# ESP8266_144.net
KiCad netlist of a schematic drawn in Altium Designer
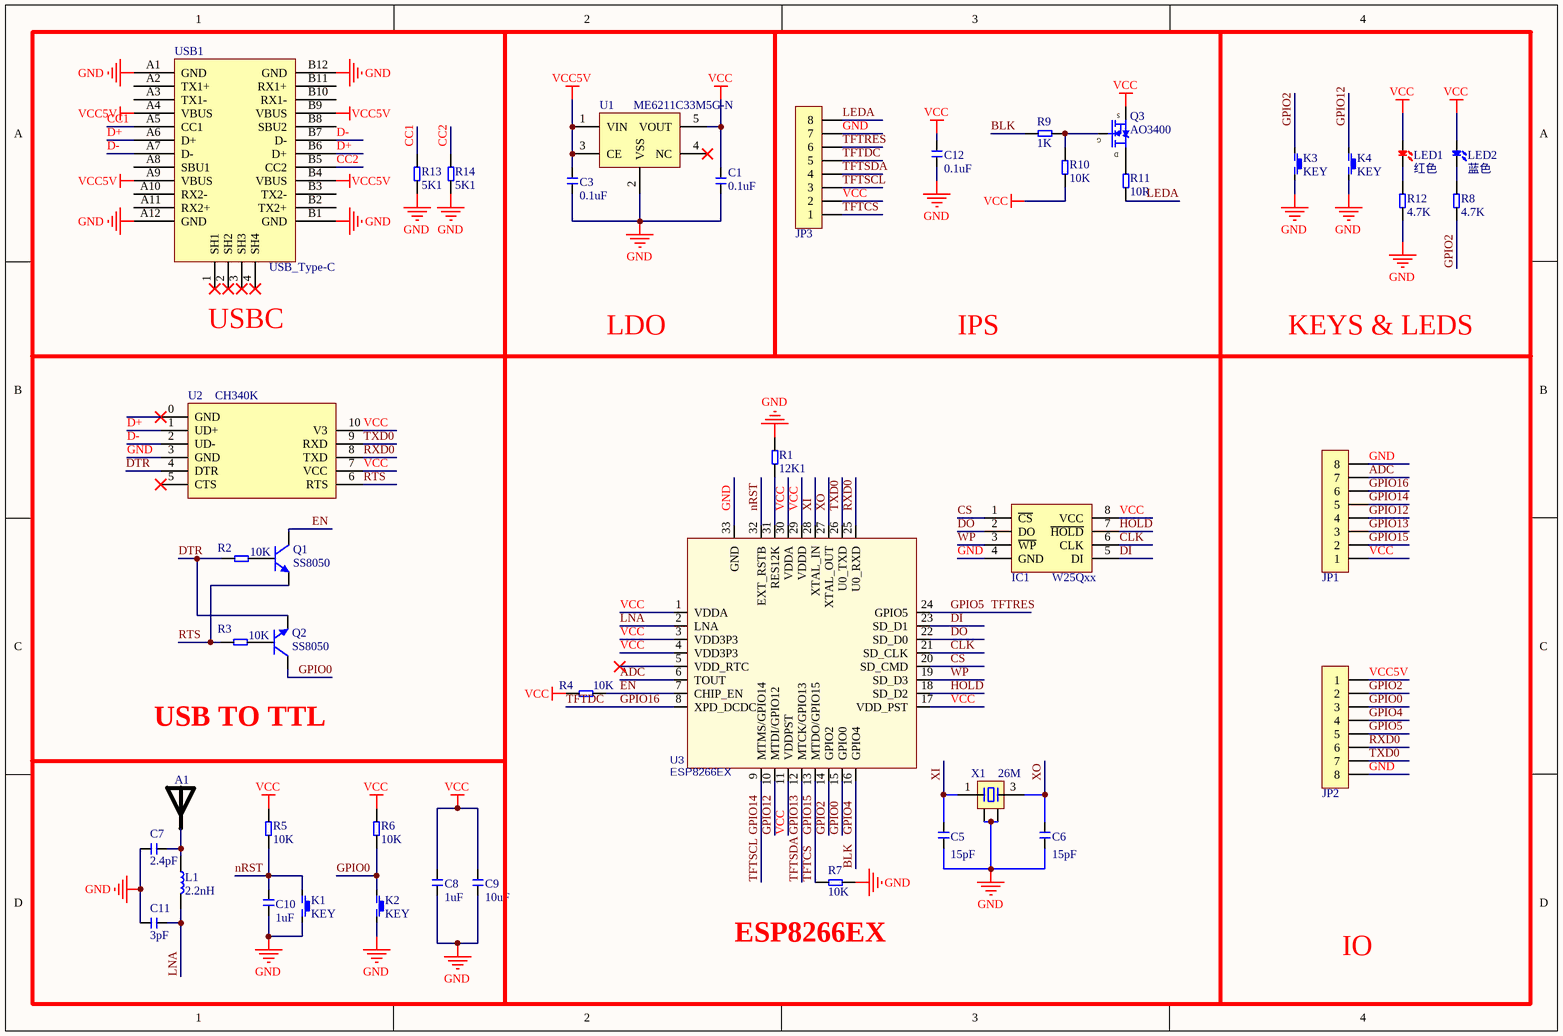
[diagram p0: ESP8266_144.SchDoc]

(export (version "E")
  (design (tool "Eeschema 10.0.6"))
  (components
    (comp (ref "A1")
      (value "RAINSUN")
      (footprint "PCBComponent_1")
      (libsource (lib "MyPcbLib") (part "ANT-Rainsun-AP5120"))
    )
    (comp (ref "C1")
      (value "0.1uF")
      (footprint "C 0603_M")
      (description "无极性贴片电容")
      (fields (field (name "版权归属") "源创客"))
      (libsource (lib "3   电容电阻电感跳线") (part "C"))
    )
    (comp (ref "C3")
      (value "0.1uF")
      (footprint "C 0603_M")
      (description "无极性贴片电容")
      (fields (field (name "版权归属") "源创客"))
      (libsource (lib "3   电容电阻电感跳线") (part "C"))
    )
    (comp (ref "C5")
      (value "15pF")
      (footprint "C 0603_M")
      (description "无极性贴片电容")
      (fields (field (name "版权归属") "源创客"))
      (libsource (lib "3   电容电阻电感跳线") (part "C"))
    )
    (comp (ref "C6")
      (value "15pF")
      (footprint "C 0603_M")
      (description "无极性贴片电容")
      (fields (field (name "版权归属") "源创客"))
      (libsource (lib "3   电容电阻电感跳线") (part "C"))
    )
    (comp (ref "C7")
      (value "2.4pF")
      (footprint "C 0603_M")
      (description "无极性贴片电容")
      (fields (field (name "版权归属") "源创客"))
      (libsource (lib "3   电容电阻电感跳线") (part "C"))
    )
    (comp (ref "C8")
      (value "1uF")
      (footprint "C 0603_M")
      (description "无极性贴片电容")
      (fields (field (name "版权归属") "源创客"))
      (libsource (lib "3   电容电阻电感跳线") (part "C"))
    )
    (comp (ref "C9")
      (value "10uF")
      (footprint "C 0603_M")
      (description "无极性贴片电容")
      (fields (field (name "版权归属") "源创客"))
      (libsource (lib "3   电容电阻电感跳线") (part "C"))
    )
    (comp (ref "C10")
      (value "1uF")
      (footprint "C 0603_M")
      (description "无极性贴片电容")
      (fields (field (name "版权归属") "源创客"))
      (libsource (lib "3   电容电阻电感跳线") (part "C"))
    )
    (comp (ref "C11")
      (value "3pF")
      (footprint "C 0603_M")
      (description "无极性贴片电容")
      (fields (field (name "版权归属") "源创客"))
      (libsource (lib "3   电容电阻电感跳线") (part "C"))
    )
    (comp (ref "C12")
      (value "0.1uF")
      (footprint "C 0603_M")
      (description "无极性贴片电容")
      (fields (field (name "版权归属") "源创客"))
      (libsource (lib "3   电容电阻电感跳线") (part "C"))
    )
    (comp (ref "IC1")
      (value "W25Qxx")
      (footprint "SOP8W_L")
      (description "外置Flash")
      (fields (field (name "版权归属") "源创客"))
      (libsource (lib "1   芯片") (part "W25Qxx"))
    )
    (comp (ref "JP1")
      (value "HDR-1X8")
      (footprint "HDR2.54-LI-8P")
      (description "8P接插件")
      (fields (field (name "版权归属") "源创客"))
      (libsource (lib "4   插接件") (part "W2.54-Header 8"))
    )
    (comp (ref "JP2")
      (value "HDR-1X8")
      (footprint "HDR2.54-LI-8P")
      (description "8P接插件")
      (fields (field (name "版权归属") "源创客"))
      (libsource (lib "") (part "W2.54-Header 8_1"))
    )
    (comp (ref "JP3")
      (value "HDR-1X8")
      (footprint "1.14 IPS")
      (description "8P接插件")
      (fields (field (name "版权归属") "源创客"))
      (libsource (lib "4   插接件") (part "W2.54-Header 8"))
    )
    (comp (ref "K1") (value "KEY") (footprint "KEY 4.2*3.2*2.5") (libsource (lib "ESP8266核心板") (part "KEY")))
    (comp (ref "K2") (value "KEY") (footprint "KEY 4.2*3.2*2.5") (libsource (lib "ESP8266核心板") (part "KEY")))
    (comp (ref "K3") (value "KEY") (footprint "KEY 4.2*3.2*2.5") (libsource (lib "ESP8266核心板") (part "KEY")))
    (comp (ref "K4") (value "KEY") (footprint "KEY 4.2*3.2*2.5") (libsource (lib "ESP8266核心板") (part "KEY")))
    (comp (ref "L1")
      (value "2.2nH")
      (footprint "L 0603_M")
      (description "小功率贴片电感")
      (fields (field (name "版权归属") "源创客"))
      (libsource (lib "3   电容电阻电感跳线") (part "L"))
    )
    (comp (ref "LED1")
      (value "红色")
      (footprint "LED 0603R_M")
      (description "贴片LED")
      (fields (field (name "版权归属") "源创客"))
      (libsource (lib "9   显示器件") (part "LED-SMD_R"))
    )
    (comp (ref "LED2")
      (value "蓝色")
      (footprint "LED 0603B_M")
      (description "贴片LED")
      (fields (field (name "版权归属") "源创客"))
      (libsource (lib "9   显示器件") (part "LED-SMD_B"))
    )
    (comp (ref "Q1")
      (value "SS8050")
      (footprint "SOT23-3M")
      (description "高频放大-NPN型")
      (fields (field (name "版权归属") "源创客"))
      (libsource (lib "6   半导体分立元件") (part "8050-SMD"))
    )
    (comp (ref "Q2")
      (value "SS8050")
      (footprint "SOT23-3M")
      (description "高频放大-NPN型")
      (fields (field (name "版权归属") "源创客"))
      (libsource (lib "6   半导体分立元件") (part "8050-SMD"))
    )
    (comp (ref "Q3")
      (value "AO3400")
      (footprint "SOT23-3M")
      (description "N沟道场效应管")
      (fields (field (name "版权归属") "源创客"))
      (libsource (lib "6   半导体分立元件") (part "AO3400"))
    )
    (comp (ref "R1") (value "12K1") (footprint "R 0603_M") (libsource (lib "measure_") (part "RES")))
    (comp (ref "R2") (value "10K") (footprint "R 0603_M") (libsource (lib "measure_") (part "RES")))
    (comp (ref "R3") (value "10K") (footprint "R 0603_M") (libsource (lib "measure_") (part "RES")))
    (comp (ref "R4") (value "10K") (footprint "R 0603_M") (libsource (lib "measure_") (part "RES")))
    (comp (ref "R5") (value "10K") (footprint "R 0603_M") (libsource (lib "measure_") (part "RES")))
    (comp (ref "R6") (value "10K") (footprint "R 0603_M") (libsource (lib "measure_") (part "RES")))
    (comp (ref "R7") (value "10K") (footprint "R 0603_M") (libsource (lib "measure_") (part "RES")))
    (comp (ref "R8") (value "4.7K") (footprint "R 0603_M") (libsource (lib "measure_") (part "RES")))
    (comp (ref "R9") (value "1K") (footprint "R 0603_M") (libsource (lib "measure_") (part "RES")))
    (comp (ref "R10") (value "10K") (footprint "R 0603_M") (libsource (lib "measure_") (part "RES")))
    (comp (ref "R11") (value "10R") (footprint "R 0603_M") (libsource (lib "measure_") (part "RES")))
    (comp (ref "R12") (value "4.7K") (footprint "R 0603_M") (libsource (lib "measure_") (part "RES")))
    (comp (ref "R13") (value "5K1") (footprint "R 0603_M") (libsource (lib "measure_") (part "RES")))
    (comp (ref "R14") (value "5K1") (footprint "R 0603_M") (libsource (lib "measure_") (part "RES")))
    (comp (ref "U1")
      (value "ME6211C33M5G-N")
      (footprint "SOT23-5N")
      (description "大电流高速LDO")
      (fields (field (name "版权归属") "源创客"))
      (libsource (lib "1   芯片") (part "XC6210B302"))
    )
    (comp (ref "U2") (value "CH340K") (footprint "CH340K") (libsource (lib "Schlib1") (part "CH340K")))
    (comp (ref "U3")
      (value "ESP8266EX")
      (footprint "QFN32 5x5_M")
      (fields (field (name "BOM_SUPPLIER PART") "C77967"))
      (libsource (lib "ESP8266核心板") (part "ESP8266EX"))
    )
    (comp (ref "USB1")
      (value "USB_Type-C")
      (footprint "TYPEC沉板")
      (libsource (lib "Vowstar_MCU") (part "USB_Type-C"))
    )
    (comp (ref "X1")
      (value "26M")
      (footprint "OSC 3225-4P")
      (description "4脚无源晶振")
      (fields (field (name "版权归属") "源创客"))
      (libsource (lib "10  保险丝 晶振") (part "XTAL-4P"))
    )
  )
  (nets
    (net (code "1") (name "/ADC") (class "Default")
      (node (ref "JP1") (pin "7") (pinfunction "7_7") (pintype "passive"))
      (node (ref "U3") (pin "6") (pinfunction "TOUT_6") (pintype "passive"))
    )
    (net (code "2") (name "/BLK") (class "Default")
      (node (ref "JP2") (pin "4") (pinfunction "4_4") (pintype "passive"))
      (node (ref "R9") (pin "1") (pintype "passive"))
      (node (ref "U3") (pin "16") (pinfunction "GPIO4_16") (pintype "passive"))
    )
    (net (code "3") (name "/CC1") (class "Default")
      (node (ref "R13") (pin "1") (pintype "passive"))
      (node (ref "USB1") (pin "A5") (pinfunction "CC1_A5") (pintype "passive"))
    )
    (net (code "4") (name "/CC2") (class "Default")
      (node (ref "R14") (pin "1") (pintype "passive"))
      (node (ref "USB1") (pin "B5") (pinfunction "CC2_B5") (pintype "passive"))
    )
    (net (code "5") (name "/CLK") (class "Default")
      (node (ref "IC1") (pin "6") (pinfunction "CLK_6") (pintype "passive"))
      (node (ref "U3") (pin "21") (pinfunction "SD_CLK_21") (pintype "passive"))
    )
    (net (code "6") (name "/CS") (class "Default")
      (node (ref "IC1") (pin "1") (pinfunction "~{CS}_1") (pintype "passive"))
      (node (ref "U3") (pin "20") (pinfunction "SD_CMD_20") (pintype "passive"))
    )
    (net (code "7") (name "/D+") (class "Default")
      (node (ref "U2") (pin "1") (pinfunction "UD+_1") (pintype "passive"))
      (node (ref "USB1") (pin "A6") (pinfunction "D+_A6") (pintype "passive"))
      (node (ref "USB1") (pin "B6") (pinfunction "D+_B6") (pintype "passive"))
    )
    (net (code "8") (name "/D-") (class "Default")
      (node (ref "U2") (pin "2") (pinfunction "UD-_2") (pintype "passive"))
      (node (ref "USB1") (pin "A7") (pinfunction "D-_A7") (pintype "passive"))
      (node (ref "USB1") (pin "B7") (pinfunction "D-_B7") (pintype "passive"))
    )
    (net (code "9") (name "/DI") (class "Default")
      (node (ref "IC1") (pin "5") (pinfunction "DI_5") (pintype "passive"))
      (node (ref "U3") (pin "23") (pinfunction "SD_D1_23") (pintype "passive"))
    )
    (net (code "10") (name "/DO") (class "Default")
      (node (ref "IC1") (pin "2") (pinfunction "DO_2") (pintype "passive"))
      (node (ref "U3") (pin "22") (pinfunction "SD_D0_22") (pintype "passive"))
    )
    (net (code "11") (name "/DTR") (class "Default")
      (node (ref "Q2") (pin "2") (pinfunction "E_2") (pintype "passive"))
      (node (ref "R2") (pin "2") (pintype "passive"))
      (node (ref "U2") (pin "4") (pinfunction "DTR_4") (pintype "passive"))
    )
    (net (code "12") (name "/EN") (class "Default")
      (node (ref "Q1") (pin "3") (pinfunction "C_3") (pintype "passive"))
      (node (ref "R4") (pin "2") (pintype "passive"))
      (node (ref "U3") (pin "7") (pinfunction "CHIP_EN_7") (pintype "passive"))
    )
    (net (code "13") (name "/GPIO0") (class "Default")
      (node (ref "JP2") (pin "3") (pinfunction "3_3") (pintype "passive"))
      (node (ref "K2") (pin "1") (pinfunction "1_1") (pintype "passive"))
      (node (ref "Q2") (pin "3") (pinfunction "C_3") (pintype "passive"))
      (node (ref "R6") (pin "2") (pintype "passive"))
      (node (ref "U3") (pin "15") (pinfunction "GPIO0_15") (pintype "passive"))
    )
    (net (code "14") (name "/GPIO2") (class "Default")
      (node (ref "JP2") (pin "2") (pinfunction "2_2") (pintype "passive"))
      (node (ref "K3") (pin "1") (pinfunction "1_1") (pintype "passive"))
      (node (ref "R8") (pin "2") (pintype "passive"))
      (node (ref "U3") (pin "14") (pinfunction "GPIO2_14") (pintype "passive"))
    )
    (net (code "15") (name "/GPIO5") (class "Default")
      (node (ref "JP2") (pin "5") (pinfunction "5_5") (pintype "passive"))
      (node (ref "JP3") (pin "6") (pinfunction "6_6") (pintype "passive"))
      (node (ref "U3") (pin "24") (pinfunction "GPIO5_24") (pintype "passive"))
    )
    (net (code "16") (name "/GPIO12") (class "Default")
      (node (ref "JP1") (pin "4") (pinfunction "4_4") (pintype "passive"))
      (node (ref "K4") (pin "1") (pinfunction "1_1") (pintype "passive"))
      (node (ref "U3") (pin "10") (pinfunction "MTDI/GPIO12_10") (pintype "passive"))
    )
    (net (code "17") (name "/GPIO13") (class "Default")
      (node (ref "JP1") (pin "3") (pinfunction "3_3") (pintype "passive"))
      (node (ref "JP3") (pin "4") (pinfunction "4_4") (pintype "passive"))
      (node (ref "U3") (pin "12") (pinfunction "MTCK/GPIO13_12") (pintype "passive"))
    )
    (net (code "18") (name "/GPIO14") (class "Default")
      (node (ref "JP1") (pin "5") (pinfunction "5_5") (pintype "passive"))
      (node (ref "JP3") (pin "3") (pinfunction "3_3") (pintype "passive"))
      (node (ref "U3") (pin "9") (pinfunction "MTMS/GPIO14_9") (pintype "passive"))
    )
    (net (code "19") (name "/GPIO15") (class "Default")
      (node (ref "JP1") (pin "2") (pinfunction "2_2") (pintype "passive"))
      (node (ref "JP3") (pin "1") (pinfunction "1_1") (pintype "passive"))
      (node (ref "R7") (pin "2") (pintype "passive"))
      (node (ref "U3") (pin "13") (pinfunction "MTDO/GPIO15_13") (pintype "passive"))
    )
    (net (code "20") (name "/GPIO16") (class "Default")
      (node (ref "JP1") (pin "6") (pinfunction "6_6") (pintype "passive"))
      (node (ref "JP3") (pin "5") (pinfunction "5_5") (pintype "passive"))
      (node (ref "U3") (pin "8") (pinfunction "XPD_DCDC_8") (pintype "passive"))
    )
    (net (code "21") (name "/HOLD") (class "Default")
      (node (ref "IC1") (pin "7") (pinfunction "~{HOLD}_7") (pintype "passive"))
      (node (ref "U3") (pin "18") (pinfunction "SD_D2_18") (pintype "passive"))
    )
    (net (code "22") (name "/LEDA") (class "Default")
      (node (ref "JP3") (pin "8") (pinfunction "8_8") (pintype "passive"))
      (node (ref "R11") (pin "1") (pintype "passive"))
    )
    (net (code "23") (name "/LNA") (class "Default")
      (node (ref "C11") (pin "1") (pinfunction "1_1") (pintype "passive"))
      (node (ref "L1") (pin "2") (pinfunction "2_2") (pintype "passive"))
      (node (ref "U3") (pin "2") (pinfunction "LNA_2") (pintype "passive"))
    )
    (net (code "24") (name "/RTS") (class "Default")
      (node (ref "Q1") (pin "2") (pinfunction "E_2") (pintype "passive"))
      (node (ref "R3") (pin "2") (pintype "passive"))
      (node (ref "U2") (pin "6") (pinfunction "RTS_6") (pintype "passive"))
    )
    (net (code "25") (name "/RXD0") (class "Default")
      (node (ref "JP2") (pin "6") (pinfunction "6_6") (pintype "passive"))
      (node (ref "U2") (pin "8") (pinfunction "TXD_8") (pintype "passive"))
      (node (ref "U3") (pin "25") (pinfunction "U0_RXD_25") (pintype "passive"))
    )
    (net (code "26") (name "/TXD0") (class "Default")
      (node (ref "JP2") (pin "7") (pinfunction "7_7") (pintype "passive"))
      (node (ref "U2") (pin "9") (pinfunction "RXD_9") (pintype "passive"))
      (node (ref "U3") (pin "26") (pinfunction "U0_TXD_26") (pintype "passive"))
    )
    (net (code "27") (name "/WP") (class "Default")
      (node (ref "IC1") (pin "3") (pinfunction "~{WP}_3") (pintype "passive"))
      (node (ref "U3") (pin "19") (pinfunction "SD_D3_19") (pintype "passive"))
    )
    (net (code "28") (name "/XI") (class "Default")
      (node (ref "C5") (pin "2") (pinfunction "2_2") (pintype "passive"))
      (node (ref "U3") (pin "28") (pinfunction "XTAL_IN_28") (pintype "passive"))
      (node (ref "X1") (pin "1") (pinfunction "1_1") (pintype "passive"))
    )
    (net (code "29") (name "/XO") (class "Default")
      (node (ref "C6") (pin "2") (pinfunction "2_2") (pintype "passive"))
      (node (ref "U3") (pin "27") (pinfunction "XTAL_OUT_27") (pintype "passive"))
      (node (ref "X1") (pin "3") (pinfunction "3_3") (pintype "passive"))
    )
    (net (code "30") (name "/nRST") (class "Default")
      (node (ref "C10") (pin "2") (pinfunction "2_2") (pintype "passive"))
      (node (ref "K1") (pin "1") (pinfunction "1_1") (pintype "passive"))
      (node (ref "R5") (pin "2") (pintype "passive"))
      (node (ref "U3") (pin "32") (pinfunction "EXT_RSTB_32") (pintype "passive"))
    )
    (net (code "31") (name "GND") (class "Default")
      (node (ref "C1") (pin "1") (pinfunction "1_1") (pintype "passive"))
      (node (ref "C10") (pin "1") (pinfunction "1_1") (pintype "passive"))
      (node (ref "C11") (pin "2") (pinfunction "2_2") (pintype "passive"))
      (node (ref "C12") (pin "1") (pinfunction "1_1") (pintype "passive"))
      (node (ref "C3") (pin "1") (pinfunction "1_1") (pintype "passive"))
      (node (ref "C5") (pin "1") (pinfunction "1_1") (pintype "passive"))
      (node (ref "C6") (pin "1") (pinfunction "1_1") (pintype "passive"))
      (node (ref "C7") (pin "2") (pinfunction "2_2") (pintype "passive"))
      (node (ref "C8") (pin "1") (pinfunction "1_1") (pintype "passive"))
      (node (ref "C9") (pin "1") (pinfunction "1_1") (pintype "passive"))
      (node (ref "IC1") (pin "4") (pinfunction "GND_4") (pintype "passive"))
      (node (ref "JP1") (pin "8") (pinfunction "8_8") (pintype "passive"))
      (node (ref "JP2") (pin "8") (pinfunction "8_8") (pintype "passive"))
      (node (ref "JP3") (pin "7") (pinfunction "7_7") (pintype "passive"))
      (node (ref "K1") (pin "3") (pinfunction "3_3") (pintype "passive"))
      (node (ref "K2") (pin "3") (pinfunction "3_3") (pintype "passive"))
      (node (ref "K3") (pin "3") (pinfunction "3_3") (pintype "passive"))
      (node (ref "K4") (pin "3") (pinfunction "3_3") (pintype "passive"))
      (node (ref "R1") (pin "1") (pintype "passive"))
      (node (ref "R12") (pin "2") (pintype "passive"))
      (node (ref "R13") (pin "2") (pintype "passive"))
      (node (ref "R14") (pin "2") (pintype "passive"))
      (node (ref "R7") (pin "1") (pintype "passive"))
      (node (ref "U1") (pin "2") (pinfunction "VSS_2") (pintype "passive"))
      (node (ref "U2") (pin "3") (pinfunction "GND_3") (pintype "passive"))
      (node (ref "U3") (pin "33") (pinfunction "GND_33") (pintype "passive"))
      (node (ref "USB1") (pin "A1") (pinfunction "GND_A1") (pintype "passive"))
      (node (ref "USB1") (pin "A12") (pinfunction "GND_A12") (pintype "passive"))
      (node (ref "USB1") (pin "B1") (pinfunction "GND_B1") (pintype "passive"))
      (node (ref "USB1") (pin "B12") (pinfunction "GND_B12") (pintype "passive"))
      (node (ref "X1") (pin "2") (pinfunction "2_2") (pintype "passive"))
      (node (ref "X1") (pin "4") (pinfunction "4_4") (pintype "passive"))
    )
    (net (code "32") (name "Net-(A1-Pad1)") (class "Default")
      (node (ref "A1") (pin "1") (pinfunction "1_1") (pintype "passive"))
      (node (ref "C7") (pin "1") (pinfunction "1_1") (pintype "passive"))
      (node (ref "L1") (pin "1") (pinfunction "1_1") (pintype "passive"))
    )
    (net (code "33") (name "Net-(LED1-K)") (class "Default")
      (node (ref "LED1") (pin "2") (pinfunction "K_2") (pintype "passive"))
      (node (ref "R12") (pin "1") (pintype "passive"))
    )
    (net (code "34") (name "Net-(LED2-K)") (class "Default")
      (node (ref "LED2") (pin "2") (pinfunction "K_2") (pintype "passive"))
      (node (ref "R8") (pin "1") (pintype "passive"))
    )
    (net (code "35") (name "Net-(Q1-B)") (class "Default")
      (node (ref "Q1") (pin "1") (pinfunction "B_1") (pintype "passive"))
      (node (ref "R2") (pin "1") (pintype "passive"))
    )
    (net (code "36") (name "Net-(Q2-B)") (class "Default")
      (node (ref "Q2") (pin "1") (pinfunction "B_1") (pintype "passive"))
      (node (ref "R3") (pin "1") (pintype "passive"))
    )
    (net (code "37") (name "Net-(Q3-D)") (class "Default")
      (node (ref "Q3") (pin "3") (pinfunction "D_3") (pintype "passive"))
      (node (ref "R11") (pin "2") (pintype "passive"))
    )
    (net (code "38") (name "Net-(Q3-G)") (class "Default")
      (node (ref "Q3") (pin "1") (pinfunction "G_1") (pintype "passive"))
      (node (ref "R10") (pin "2") (pintype "passive"))
      (node (ref "R9") (pin "2") (pintype "passive"))
    )
    (net (code "39") (name "Net-(U3-RES12K)") (class "Default")
      (node (ref "R1") (pin "2") (pintype "passive"))
      (node (ref "U3") (pin "31") (pinfunction "RES12K_31") (pintype "passive"))
    )
    (net (code "40") (name "VCC") (class "Default")
      (node (ref "C1") (pin "2") (pinfunction "2_2") (pintype "passive"))
      (node (ref "C12") (pin "2") (pinfunction "2_2") (pintype "passive"))
      (node (ref "C8") (pin "2") (pinfunction "2_2") (pintype "passive"))
      (node (ref "C9") (pin "2") (pinfunction "2_2") (pintype "passive"))
      (node (ref "IC1") (pin "8") (pinfunction "VCC_8") (pintype "passive"))
      (node (ref "JP1") (pin "1") (pinfunction "1_1") (pintype "passive"))
      (node (ref "JP3") (pin "2") (pinfunction "2_2") (pintype "passive"))
      (node (ref "LED1") (pin "1") (pinfunction "A_1") (pintype "passive"))
      (node (ref "LED2") (pin "1") (pinfunction "A_1") (pintype "passive"))
      (node (ref "Q3") (pin "2") (pinfunction "S_2") (pintype "passive"))
      (node (ref "R10") (pin "1") (pintype "passive"))
      (node (ref "R4") (pin "1") (pintype "passive"))
      (node (ref "R5") (pin "1") (pintype "passive"))
      (node (ref "R6") (pin "1") (pintype "passive"))
      (node (ref "U1") (pin "5") (pinfunction "VOUT_5") (pintype "passive"))
      (node (ref "U2") (pin "10") (pinfunction "V3_10") (pintype "passive"))
      (node (ref "U2") (pin "7") (pinfunction "VCC_7") (pintype "passive"))
      (node (ref "U3") (pin "1") (pinfunction "VDDA_1") (pintype "passive"))
      (node (ref "U3") (pin "11") (pinfunction "VDDPST_11") (pintype "passive"))
      (node (ref "U3") (pin "17") (pinfunction "VDD_PST_17") (pintype "passive"))
      (node (ref "U3") (pin "29") (pinfunction "VDDD_29") (pintype "passive"))
      (node (ref "U3") (pin "3") (pinfunction "VDD3P3_3") (pintype "passive"))
      (node (ref "U3") (pin "30") (pinfunction "VDDA_30") (pintype "passive"))
      (node (ref "U3") (pin "4") (pinfunction "VDD3P3_4") (pintype "passive"))
    )
    (net (code "41") (name "VCC5V") (class "Default")
      (node (ref "C3") (pin "2") (pinfunction "2_2") (pintype "passive"))
      (node (ref "JP2") (pin "1") (pinfunction "1_1") (pintype "passive"))
      (node (ref "U1") (pin "1") (pinfunction "VIN_1") (pintype "passive"))
      (node (ref "U1") (pin "3") (pinfunction "CE_3") (pintype "passive"))
      (node (ref "USB1") (pin "A4") (pinfunction "VBUS_A4") (pintype "passive"))
      (node (ref "USB1") (pin "A9") (pinfunction "VBUS_A9") (pintype "passive"))
      (node (ref "USB1") (pin "B4") (pinfunction "VBUS_B4") (pintype "passive"))
      (node (ref "USB1") (pin "B9") (pinfunction "VBUS_B9") (pintype "passive"))
    )
    (net (code "42") (name "unconnected-(U1-NC-Pad4)") (class "Default")
      (node (ref "U1") (pin "4") (pinfunction "NC_4") (pintype "passive+no_connect"))
    )
    (net (code "43") (name "unconnected-(U2-CTS-Pad5)") (class "Default")
      (node (ref "U2") (pin "5") (pinfunction "CTS_5") (pintype "passive+no_connect"))
    )
    (net (code "44") (name "unconnected-(U2-GND-Pad0)") (class "Default")
      (node (ref "U2") (pin "0") (pinfunction "GND_0") (pintype "passive+no_connect"))
    )
    (net (code "45") (name "unconnected-(U3-VDD_RTC-Pad5)") (class "Default")
      (node (ref "U3") (pin "5") (pinfunction "VDD_RTC_5") (pintype "passive+no_connect"))
    )
    (net (code "46") (name "unconnected-(USB1-RX1+-PadB11)") (class "Default")
      (node (ref "USB1") (pin "B11") (pinfunction "RX1+_B11") (pintype "passive"))
    )
    (net (code "47") (name "unconnected-(USB1-RX1--PadB10)") (class "Default")
      (node (ref "USB1") (pin "B10") (pinfunction "RX1-_B10") (pintype "passive"))
    )
    (net (code "48") (name "unconnected-(USB1-RX2+-PadA11)") (class "Default")
      (node (ref "USB1") (pin "A11") (pinfunction "RX2+_A11") (pintype "passive"))
    )
    (net (code "49") (name "unconnected-(USB1-RX2--PadA10)") (class "Default")
      (node (ref "USB1") (pin "A10") (pinfunction "RX2-_A10") (pintype "passive"))
    )
    (net (code "50") (name "unconnected-(USB1-SBU1-PadA8)") (class "Default")
      (node (ref "USB1") (pin "A8") (pinfunction "SBU1_A8") (pintype "passive"))
    )
    (net (code "51") (name "unconnected-(USB1-SBU2-PadB8)") (class "Default")
      (node (ref "USB1") (pin "B8") (pinfunction "SBU2_B8") (pintype "passive"))
    )
    (net (code "52") (name "unconnected-(USB1-SH1-Pad1)") (class "Default")
      (node (ref "USB1") (pin "1") (pinfunction "SH1_1") (pintype "passive+no_connect"))
    )
    (net (code "53") (name "unconnected-(USB1-SH2-Pad2)") (class "Default")
      (node (ref "USB1") (pin "2") (pinfunction "SH2_2") (pintype "passive+no_connect"))
    )
    (net (code "54") (name "unconnected-(USB1-SH3-Pad3)") (class "Default")
      (node (ref "USB1") (pin "3") (pinfunction "SH3_3") (pintype "passive+no_connect"))
    )
    (net (code "55") (name "unconnected-(USB1-SH4-Pad4)") (class "Default")
      (node (ref "USB1") (pin "4") (pinfunction "SH4_4") (pintype "passive+no_connect"))
    )
    (net (code "56") (name "unconnected-(USB1-TX1+-PadA2)") (class "Default")
      (node (ref "USB1") (pin "A2") (pinfunction "TX1+_A2") (pintype "passive"))
    )
    (net (code "57") (name "unconnected-(USB1-TX1--PadA3)") (class "Default")
      (node (ref "USB1") (pin "A3") (pinfunction "TX1-_A3") (pintype "passive"))
    )
    (net (code "58") (name "unconnected-(USB1-TX2+-PadB2)") (class "Default")
      (node (ref "USB1") (pin "B2") (pinfunction "TX2+_B2") (pintype "passive"))
    )
    (net (code "59") (name "unconnected-(USB1-TX2--PadB3)") (class "Default")
      (node (ref "USB1") (pin "B3") (pinfunction "TX2-_B3") (pintype "passive"))
    )
  )
)
